# Interface.net
KiCad netlist of a schematic drawn in Altium Designer
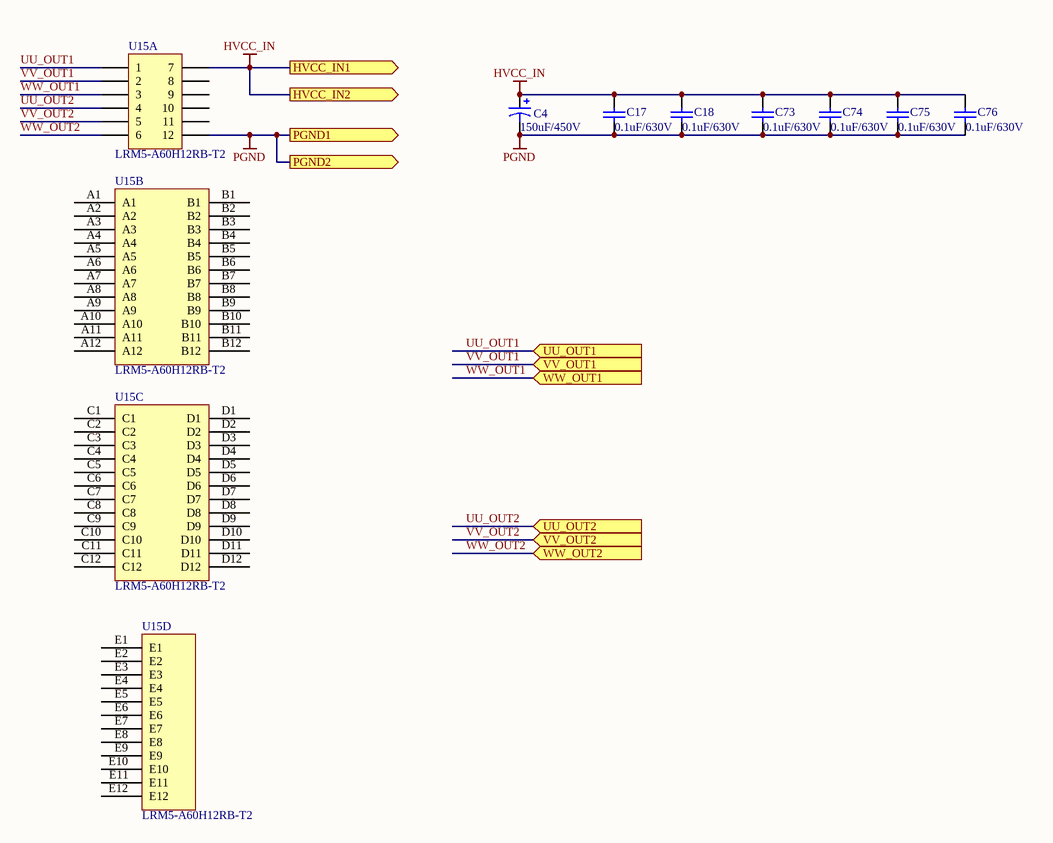
[diagram p0: Interface.SchDoc]

(export (version "E")
  (design (tool "Eeschema 10.0.6"))
  (components
    (comp (ref "C4")
      (value "150uF/450V")
      (footprint "MKP3D-450V-140UF-1")
      (description "Polarized Capacitor (Radial)")
      (fields (field (name "PUBLISHER") "Altium Limited"))
      (libsource (lib "Miscellaneous Devices") (part "Cap Pol1"))
    )
    (comp (ref "C17")
      (value "0.1uF/630V")
      (footprint "WP_1812")
      (description "Capacitor (Semiconductor SIM Model)")
      (fields (field (name "PUBLISHER") "Altium Limited"))
      (libsource (lib "Miscellaneous Devices") (part "Cap Semi"))
    )
    (comp (ref "C18")
      (value "0.1uF/630V")
      (footprint "WP_1812")
      (description "Capacitor (Semiconductor SIM Model)")
      (fields (field (name "PUBLISHER") "Altium Limited"))
      (libsource (lib "Miscellaneous Devices") (part "Cap Semi"))
    )
    (comp (ref "C73")
      (value "0.1uF/630V")
      (footprint "WP_1812")
      (description "Capacitor (Semiconductor SIM Model)")
      (fields (field (name "PUBLISHER") "Altium Limited"))
      (libsource (lib "Miscellaneous Devices") (part "Cap Semi"))
    )
    (comp (ref "C74")
      (value "0.1uF/630V")
      (footprint "WP_1812")
      (description "Capacitor (Semiconductor SIM Model)")
      (fields (field (name "PUBLISHER") "Altium Limited"))
      (libsource (lib "Miscellaneous Devices") (part "Cap Semi"))
    )
    (comp (ref "C75")
      (value "0.1uF/630V")
      (footprint "WP_1812")
      (description "Capacitor (Semiconductor SIM Model)")
      (fields (field (name "PUBLISHER") "Altium Limited"))
      (libsource (lib "Miscellaneous Devices") (part "Cap Semi"))
    )
    (comp (ref "C76")
      (value "0.1uF/630V")
      (footprint "WP_1812")
      (description "Capacitor (Semiconductor SIM Model)")
      (fields (field (name "PUBLISHER") "Altium Limited"))
      (libsource (lib "Miscellaneous Devices") (part "Cap Semi"))
    )
    (comp (ref "U15")
      (value "LRM5-A60H12RB-T2")
      (footprint "WP_LRM5-A60H12RB-T2")
      (libsource (lib "Interface2") (part "MULTI_HEADER"))
    )
  )
  (nets
    (net (code "1") (name "/UU_OUT1") (class "Default")
      (node (ref "U15") (pin "1") (pinfunction "1_1") (pintype "passive"))
    )
    (net (code "2") (name "/UU_OUT2") (class "Default")
      (node (ref "U15") (pin "4") (pinfunction "4_4") (pintype "passive"))
    )
    (net (code "3") (name "/VV_OUT1") (class "Default")
      (node (ref "U15") (pin "2") (pinfunction "2_2") (pintype "passive"))
    )
    (net (code "4") (name "/VV_OUT2") (class "Default")
      (node (ref "U15") (pin "5") (pinfunction "5_5") (pintype "passive"))
    )
    (net (code "5") (name "/WW_OUT1") (class "Default")
      (node (ref "U15") (pin "3") (pinfunction "3_3") (pintype "passive"))
    )
    (net (code "6") (name "/WW_OUT2") (class "Default")
      (node (ref "U15") (pin "6") (pinfunction "6_6") (pintype "passive"))
    )
    (net (code "7") (name "HVCC_IN") (class "Default")
      (node (ref "C17") (pin "2") (pinfunction "2_2") (pintype "passive"))
      (node (ref "C18") (pin "2") (pinfunction "2_2") (pintype "passive"))
      (node (ref "C4") (pin "1") (pinfunction "1_1") (pintype "passive"))
      (node (ref "C73") (pin "2") (pinfunction "2_2") (pintype "passive"))
      (node (ref "C74") (pin "2") (pinfunction "2_2") (pintype "passive"))
      (node (ref "C75") (pin "2") (pinfunction "2_2") (pintype "passive"))
      (node (ref "C76") (pin "2") (pinfunction "2_2") (pintype "passive"))
      (node (ref "U15") (pin "7") (pinfunction "7_7") (pintype "passive"))
    )
    (net (code "8") (name "PGND") (class "Default")
      (node (ref "C17") (pin "1") (pinfunction "1_1") (pintype "passive"))
      (node (ref "C18") (pin "1") (pinfunction "1_1") (pintype "passive"))
      (node (ref "C4") (pin "2") (pinfunction "2_2") (pintype "passive"))
      (node (ref "C73") (pin "1") (pinfunction "1_1") (pintype "passive"))
      (node (ref "C74") (pin "1") (pinfunction "1_1") (pintype "passive"))
      (node (ref "C75") (pin "1") (pinfunction "1_1") (pintype "passive"))
      (node (ref "C76") (pin "1") (pinfunction "1_1") (pintype "passive"))
      (node (ref "U15") (pin "12") (pinfunction "12_12") (pintype "passive"))
    )
    (net (code "9") (name "unconnected-(U15-Pad8)") (class "Default")
      (node (ref "U15") (pin "8") (pinfunction "8_8") (pintype "passive"))
    )
    (net (code "10") (name "unconnected-(U15-Pad9)") (class "Default")
      (node (ref "U15") (pin "9") (pinfunction "9_9") (pintype "passive"))
    )
    (net (code "11") (name "unconnected-(U15-Pad10)") (class "Default")
      (node (ref "U15") (pin "10") (pinfunction "10_10") (pintype "passive"))
    )
    (net (code "12") (name "unconnected-(U15-Pad11)") (class "Default")
      (node (ref "U15") (pin "11") (pinfunction "11_11") (pintype "passive"))
    )
    (net (code "13") (name "unconnected-(U15-PadA1)") (class "Default")
      (node (ref "U15") (pin "A1") (pinfunction "A1_A1") (pintype "passive"))
    )
    (net (code "14") (name "unconnected-(U15-PadA2)") (class "Default")
      (node (ref "U15") (pin "A2") (pinfunction "A2_A2") (pintype "passive"))
    )
    (net (code "15") (name "unconnected-(U15-PadA3)") (class "Default")
      (node (ref "U15") (pin "A3") (pinfunction "A3_A3") (pintype "passive"))
    )
    (net (code "16") (name "unconnected-(U15-PadA4)") (class "Default")
      (node (ref "U15") (pin "A4") (pinfunction "A4_A4") (pintype "passive"))
    )
    (net (code "17") (name "unconnected-(U15-PadA5)") (class "Default")
      (node (ref "U15") (pin "A5") (pinfunction "A5_A5") (pintype "passive"))
    )
    (net (code "18") (name "unconnected-(U15-PadA6)") (class "Default")
      (node (ref "U15") (pin "A6") (pinfunction "A6_A6") (pintype "passive"))
    )
    (net (code "19") (name "unconnected-(U15-PadA7)") (class "Default")
      (node (ref "U15") (pin "A7") (pinfunction "A7_A7") (pintype "passive"))
    )
    (net (code "20") (name "unconnected-(U15-PadA8)") (class "Default")
      (node (ref "U15") (pin "A8") (pinfunction "A8_A8") (pintype "passive"))
    )
    (net (code "21") (name "unconnected-(U15-PadA9)") (class "Default")
      (node (ref "U15") (pin "A9") (pinfunction "A9_A9") (pintype "passive"))
    )
    (net (code "22") (name "unconnected-(U15-PadA10)") (class "Default")
      (node (ref "U15") (pin "A10") (pinfunction "A10_A10") (pintype "passive"))
    )
    (net (code "23") (name "unconnected-(U15-PadA11)") (class "Default")
      (node (ref "U15") (pin "A11") (pinfunction "A11_A11") (pintype "passive"))
    )
    (net (code "24") (name "unconnected-(U15-PadA12)") (class "Default")
      (node (ref "U15") (pin "A12") (pinfunction "A12_A12") (pintype "passive"))
    )
    (net (code "25") (name "unconnected-(U15-PadB1)") (class "Default")
      (node (ref "U15") (pin "B1") (pinfunction "B1_B1") (pintype "passive"))
    )
    (net (code "26") (name "unconnected-(U15-PadB2)") (class "Default")
      (node (ref "U15") (pin "B2") (pinfunction "B2_B2") (pintype "passive"))
    )
    (net (code "27") (name "unconnected-(U15-PadB3)") (class "Default")
      (node (ref "U15") (pin "B3") (pinfunction "B3_B3") (pintype "passive"))
    )
    (net (code "28") (name "unconnected-(U15-PadB4)") (class "Default")
      (node (ref "U15") (pin "B4") (pinfunction "B4_B4") (pintype "passive"))
    )
    (net (code "29") (name "unconnected-(U15-PadB5)") (class "Default")
      (node (ref "U15") (pin "B5") (pinfunction "B5_B5") (pintype "passive"))
    )
    (net (code "30") (name "unconnected-(U15-PadB6)") (class "Default")
      (node (ref "U15") (pin "B6") (pinfunction "B6_B6") (pintype "passive"))
    )
    (net (code "31") (name "unconnected-(U15-PadB7)") (class "Default")
      (node (ref "U15") (pin "B7") (pinfunction "B7_B7") (pintype "passive"))
    )
    (net (code "32") (name "unconnected-(U15-PadB8)") (class "Default")
      (node (ref "U15") (pin "B8") (pinfunction "B8_B8") (pintype "passive"))
    )
    (net (code "33") (name "unconnected-(U15-PadB9)") (class "Default")
      (node (ref "U15") (pin "B9") (pinfunction "B9_B9") (pintype "passive"))
    )
    (net (code "34") (name "unconnected-(U15-PadB10)") (class "Default")
      (node (ref "U15") (pin "B10") (pinfunction "B10_B10") (pintype "passive"))
    )
    (net (code "35") (name "unconnected-(U15-PadB11)") (class "Default")
      (node (ref "U15") (pin "B11") (pinfunction "B11_B11") (pintype "passive"))
    )
    (net (code "36") (name "unconnected-(U15-PadB12)") (class "Default")
      (node (ref "U15") (pin "B12") (pinfunction "B12_B12") (pintype "passive"))
    )
    (net (code "37") (name "unconnected-(U15-PadC1)") (class "Default")
      (node (ref "U15") (pin "C1") (pinfunction "C1_C1") (pintype "passive"))
    )
    (net (code "38") (name "unconnected-(U15-PadC2)") (class "Default")
      (node (ref "U15") (pin "C2") (pinfunction "C2_C2") (pintype "passive"))
    )
    (net (code "39") (name "unconnected-(U15-PadC3)") (class "Default")
      (node (ref "U15") (pin "C3") (pinfunction "C3_C3") (pintype "passive"))
    )
    (net (code "40") (name "unconnected-(U15-PadC4)") (class "Default")
      (node (ref "U15") (pin "C4") (pinfunction "C4_C4") (pintype "passive"))
    )
    (net (code "41") (name "unconnected-(U15-PadC5)") (class "Default")
      (node (ref "U15") (pin "C5") (pinfunction "C5_C5") (pintype "passive"))
    )
    (net (code "42") (name "unconnected-(U15-PadC6)") (class "Default")
      (node (ref "U15") (pin "C6") (pinfunction "C6_C6") (pintype "passive"))
    )
    (net (code "43") (name "unconnected-(U15-PadC7)") (class "Default")
      (node (ref "U15") (pin "C7") (pinfunction "C7_C7") (pintype "passive"))
    )
    (net (code "44") (name "unconnected-(U15-PadC8)") (class "Default")
      (node (ref "U15") (pin "C8") (pinfunction "C8_C8") (pintype "passive"))
    )
    (net (code "45") (name "unconnected-(U15-PadC9)") (class "Default")
      (node (ref "U15") (pin "C9") (pinfunction "C9_C9") (pintype "passive"))
    )
    (net (code "46") (name "unconnected-(U15-PadC10)") (class "Default")
      (node (ref "U15") (pin "C10") (pinfunction "C10_C10") (pintype "passive"))
    )
    (net (code "47") (name "unconnected-(U15-PadC11)") (class "Default")
      (node (ref "U15") (pin "C11") (pinfunction "C11_C11") (pintype "passive"))
    )
    (net (code "48") (name "unconnected-(U15-PadC12)") (class "Default")
      (node (ref "U15") (pin "C12") (pinfunction "C12_C12") (pintype "passive"))
    )
    (net (code "49") (name "unconnected-(U15-PadD1)") (class "Default")
      (node (ref "U15") (pin "D1") (pinfunction "D1_D1") (pintype "passive"))
    )
    (net (code "50") (name "unconnected-(U15-PadD2)") (class "Default")
      (node (ref "U15") (pin "D2") (pinfunction "D2_D2") (pintype "passive"))
    )
    (net (code "51") (name "unconnected-(U15-PadD3)") (class "Default")
      (node (ref "U15") (pin "D3") (pinfunction "D3_D3") (pintype "passive"))
    )
    (net (code "52") (name "unconnected-(U15-PadD4)") (class "Default")
      (node (ref "U15") (pin "D4") (pinfunction "D4_D4") (pintype "passive"))
    )
    (net (code "53") (name "unconnected-(U15-PadD5)") (class "Default")
      (node (ref "U15") (pin "D5") (pinfunction "D5_D5") (pintype "passive"))
    )
    (net (code "54") (name "unconnected-(U15-PadD6)") (class "Default")
      (node (ref "U15") (pin "D6") (pinfunction "D6_D6") (pintype "passive"))
    )
    (net (code "55") (name "unconnected-(U15-PadD7)") (class "Default")
      (node (ref "U15") (pin "D7") (pinfunction "D7_D7") (pintype "passive"))
    )
    (net (code "56") (name "unconnected-(U15-PadD8)") (class "Default")
      (node (ref "U15") (pin "D8") (pinfunction "D8_D8") (pintype "passive"))
    )
    (net (code "57") (name "unconnected-(U15-PadD9)") (class "Default")
      (node (ref "U15") (pin "D9") (pinfunction "D9_D9") (pintype "passive"))
    )
    (net (code "58") (name "unconnected-(U15-PadD10)") (class "Default")
      (node (ref "U15") (pin "D10") (pinfunction "D10_D10") (pintype "passive"))
    )
    (net (code "59") (name "unconnected-(U15-PadD11)") (class "Default")
      (node (ref "U15") (pin "D11") (pinfunction "D11_D11") (pintype "passive"))
    )
    (net (code "60") (name "unconnected-(U15-PadD12)") (class "Default")
      (node (ref "U15") (pin "D12") (pinfunction "D12_D12") (pintype "passive"))
    )
    (net (code "61") (name "unconnected-(U15-PadE1)") (class "Default")
      (node (ref "U15") (pin "E1") (pinfunction "E1_E1") (pintype "passive"))
    )
    (net (code "62") (name "unconnected-(U15-PadE2)") (class "Default")
      (node (ref "U15") (pin "E2") (pinfunction "E2_E2") (pintype "passive"))
    )
    (net (code "63") (name "unconnected-(U15-PadE3)") (class "Default")
      (node (ref "U15") (pin "E3") (pinfunction "E3_E3") (pintype "passive"))
    )
    (net (code "64") (name "unconnected-(U15-PadE4)") (class "Default")
      (node (ref "U15") (pin "E4") (pinfunction "E4_E4") (pintype "passive"))
    )
    (net (code "65") (name "unconnected-(U15-PadE5)") (class "Default")
      (node (ref "U15") (pin "E5") (pinfunction "E5_E5") (pintype "passive"))
    )
    (net (code "66") (name "unconnected-(U15-PadE6)") (class "Default")
      (node (ref "U15") (pin "E6") (pinfunction "E6_E6") (pintype "passive"))
    )
    (net (code "67") (name "unconnected-(U15-PadE7)") (class "Default")
      (node (ref "U15") (pin "E7") (pinfunction "E7_E7") (pintype "passive"))
    )
    (net (code "68") (name "unconnected-(U15-PadE8)") (class "Default")
      (node (ref "U15") (pin "E8") (pinfunction "E8_E8") (pintype "passive"))
    )
    (net (code "69") (name "unconnected-(U15-PadE9)") (class "Default")
      (node (ref "U15") (pin "E9") (pinfunction "E9_E9") (pintype "passive"))
    )
    (net (code "70") (name "unconnected-(U15-PadE10)") (class "Default")
      (node (ref "U15") (pin "E10") (pinfunction "E10_E10") (pintype "passive"))
    )
    (net (code "71") (name "unconnected-(U15-PadE11)") (class "Default")
      (node (ref "U15") (pin "E11") (pinfunction "E11_E11") (pintype "passive"))
    )
    (net (code "72") (name "unconnected-(U15-PadE12)") (class "Default")
      (node (ref "U15") (pin "E12") (pinfunction "E12_E12") (pintype "passive"))
    )
  )
)
